# AST1024.net
KiCad netlist of a schematic drawn in EAGLE
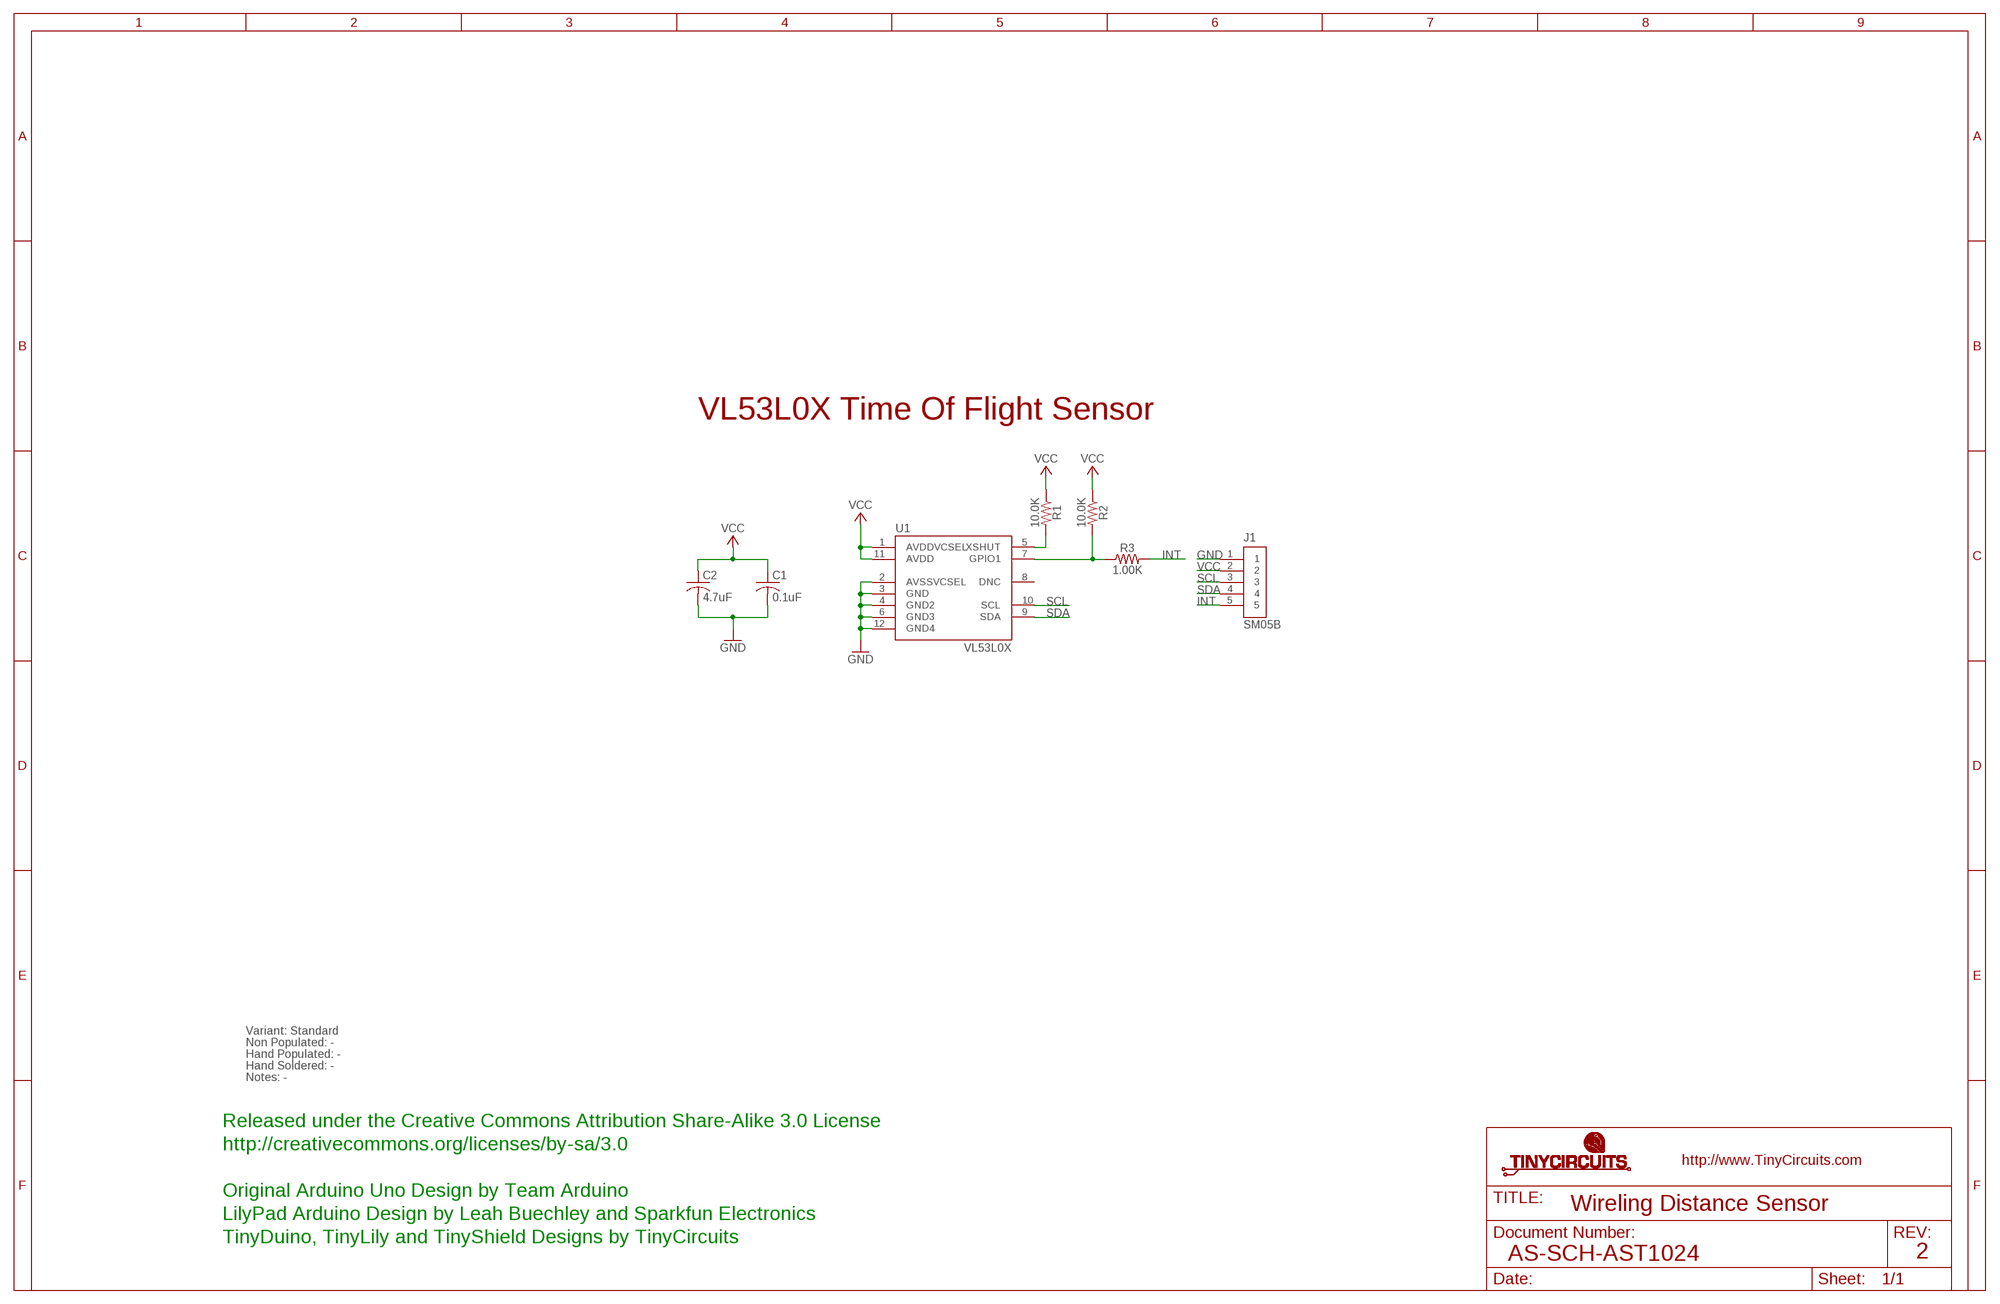
[diagram p0: schematic, sheet 1]

(export (version "E")
  (design (tool "Eeschema 10.0.6"))
  (components
    (comp (ref "C1")
      (value "0.1uF")
      (footprint "eagle-import:C0402")
      (fields (field (name "PARTNO") "AS-ITM-00008"))
      (libsource (lib "eagle-import") (part "AS-ITM-00008"))
    )
    (comp (ref "C2")
      (value "4.7uF")
      (footprint "eagle-import:C0603")
      (fields (field (name "PARTNO") "AS-ITM-00088") (field (name "PARTNO_1") "AS-ITM-00088"))
      (libsource (lib "eagle-import") (part "AS-ITM-00088"))
    )
    (comp (ref "J1")
      (value "SM05B")
      (footprint "eagle-import:JST_SH_5X1_EDGE")
      (fields (field (name "PARTNO") "AS-ITM-00340"))
      (libsource (lib "eagle-import") (part "AS-ITM-00340EDGE"))
    )
    (comp (ref "R1")
      (value "10.0K")
      (footprint "eagle-import:0402")
      (fields (field (name "PARTNO") "AS-ITM-00032"))
      (libsource (lib "eagle-import") (part "AS-ITM-00032"))
    )
    (comp (ref "R2")
      (value "10.0K")
      (footprint "eagle-import:0402")
      (fields (field (name "PARTNO") "AS-ITM-00032") (field (name "PARTNO_1") "AS-ITM-00032"))
      (libsource (lib "eagle-import") (part "AS-ITM-00032"))
    )
    (comp (ref "R3")
      (value "1.00K")
      (footprint "eagle-import:0402")
      (fields (field (name "PARTNO") "AS-ITM-00003") (field (name "PARTNO_1") "AS-ITM-00003"))
      (libsource (lib "eagle-import") (part "AS-ITM-00003"))
    )
    (comp (ref "U1")
      (value "VL53L0X")
      (footprint "eagle-import:VL53L0X")
      (fields (field (name "PARTNO") "AS-ITM-00338"))
      (libsource (lib "eagle-import") (part "AS-ITM-00338"))
    )
  )
  (nets
    (net (code "1") (name "/INT") (class "Default")
      (node (ref "J1") (pin "5") (pinfunction "5_5") (pintype "bidirectional"))
      (node (ref "R3") (pin "2") (pinfunction "2_2") (pintype "passive"))
    )
    (net (code "2") (name "/SCL") (class "Default")
      (node (ref "J1") (pin "3") (pinfunction "3_3") (pintype "bidirectional"))
      (node (ref "U1") (pin "10") (pinfunction "SCL_10") (pintype "bidirectional"))
    )
    (net (code "3") (name "/SDA") (class "Default")
      (node (ref "J1") (pin "4") (pinfunction "4_4") (pintype "bidirectional"))
      (node (ref "U1") (pin "9") (pinfunction "SDA_9") (pintype "bidirectional"))
    )
    (net (code "4") (name "GND") (class "Default")
      (node (ref "C1") (pin "2") (pinfunction "2_2") (pintype "passive"))
      (node (ref "C2") (pin "2") (pinfunction "2_2") (pintype "passive"))
      (node (ref "J1") (pin "1") (pinfunction "1_1") (pintype "bidirectional"))
      (node (ref "U1") (pin "12") (pinfunction "GND4_12") (pintype "bidirectional"))
      (node (ref "U1") (pin "2") (pinfunction "AVSSVCSEL_2") (pintype "bidirectional"))
      (node (ref "U1") (pin "3") (pinfunction "GND_3") (pintype "bidirectional"))
      (node (ref "U1") (pin "4") (pinfunction "GND2_4") (pintype "bidirectional"))
      (node (ref "U1") (pin "6") (pinfunction "GND3_6") (pintype "bidirectional"))
    )
    (net (code "5") (name "Net-(U1-GPIO1)") (class "Default")
      (node (ref "R2") (pin "2") (pinfunction "2_2") (pintype "passive"))
      (node (ref "R3") (pin "1") (pinfunction "1_1") (pintype "passive"))
      (node (ref "U1") (pin "7") (pinfunction "GPIO1_7") (pintype "bidirectional"))
    )
    (net (code "6") (name "Net-(U1-XSHUT)") (class "Default")
      (node (ref "R1") (pin "2") (pinfunction "2_2") (pintype "passive"))
      (node (ref "U1") (pin "5") (pinfunction "XSHUT_5") (pintype "bidirectional"))
    )
    (net (code "7") (name "VCC") (class "Default")
      (node (ref "C1") (pin "1") (pinfunction "1_1") (pintype "passive"))
      (node (ref "C2") (pin "1") (pinfunction "1_1") (pintype "passive"))
      (node (ref "J1") (pin "2") (pinfunction "2_2") (pintype "bidirectional"))
      (node (ref "R1") (pin "1") (pinfunction "1_1") (pintype "passive"))
      (node (ref "R2") (pin "1") (pinfunction "1_1") (pintype "passive"))
      (node (ref "U1") (pin "1") (pinfunction "AVDDVCSEL_1") (pintype "bidirectional"))
      (node (ref "U1") (pin "11") (pinfunction "AVDD_11") (pintype "bidirectional"))
    )
    (net (code "8") (name "unconnected-(U1-DNC-Pad8)") (class "Default")
      (node (ref "U1") (pin "8") (pinfunction "DNC_8") (pintype "bidirectional"))
    )
  )
)
